# STorM32_BGC_mpu_module_v009.net
KiCad netlist of a schematic drawn in EAGLE
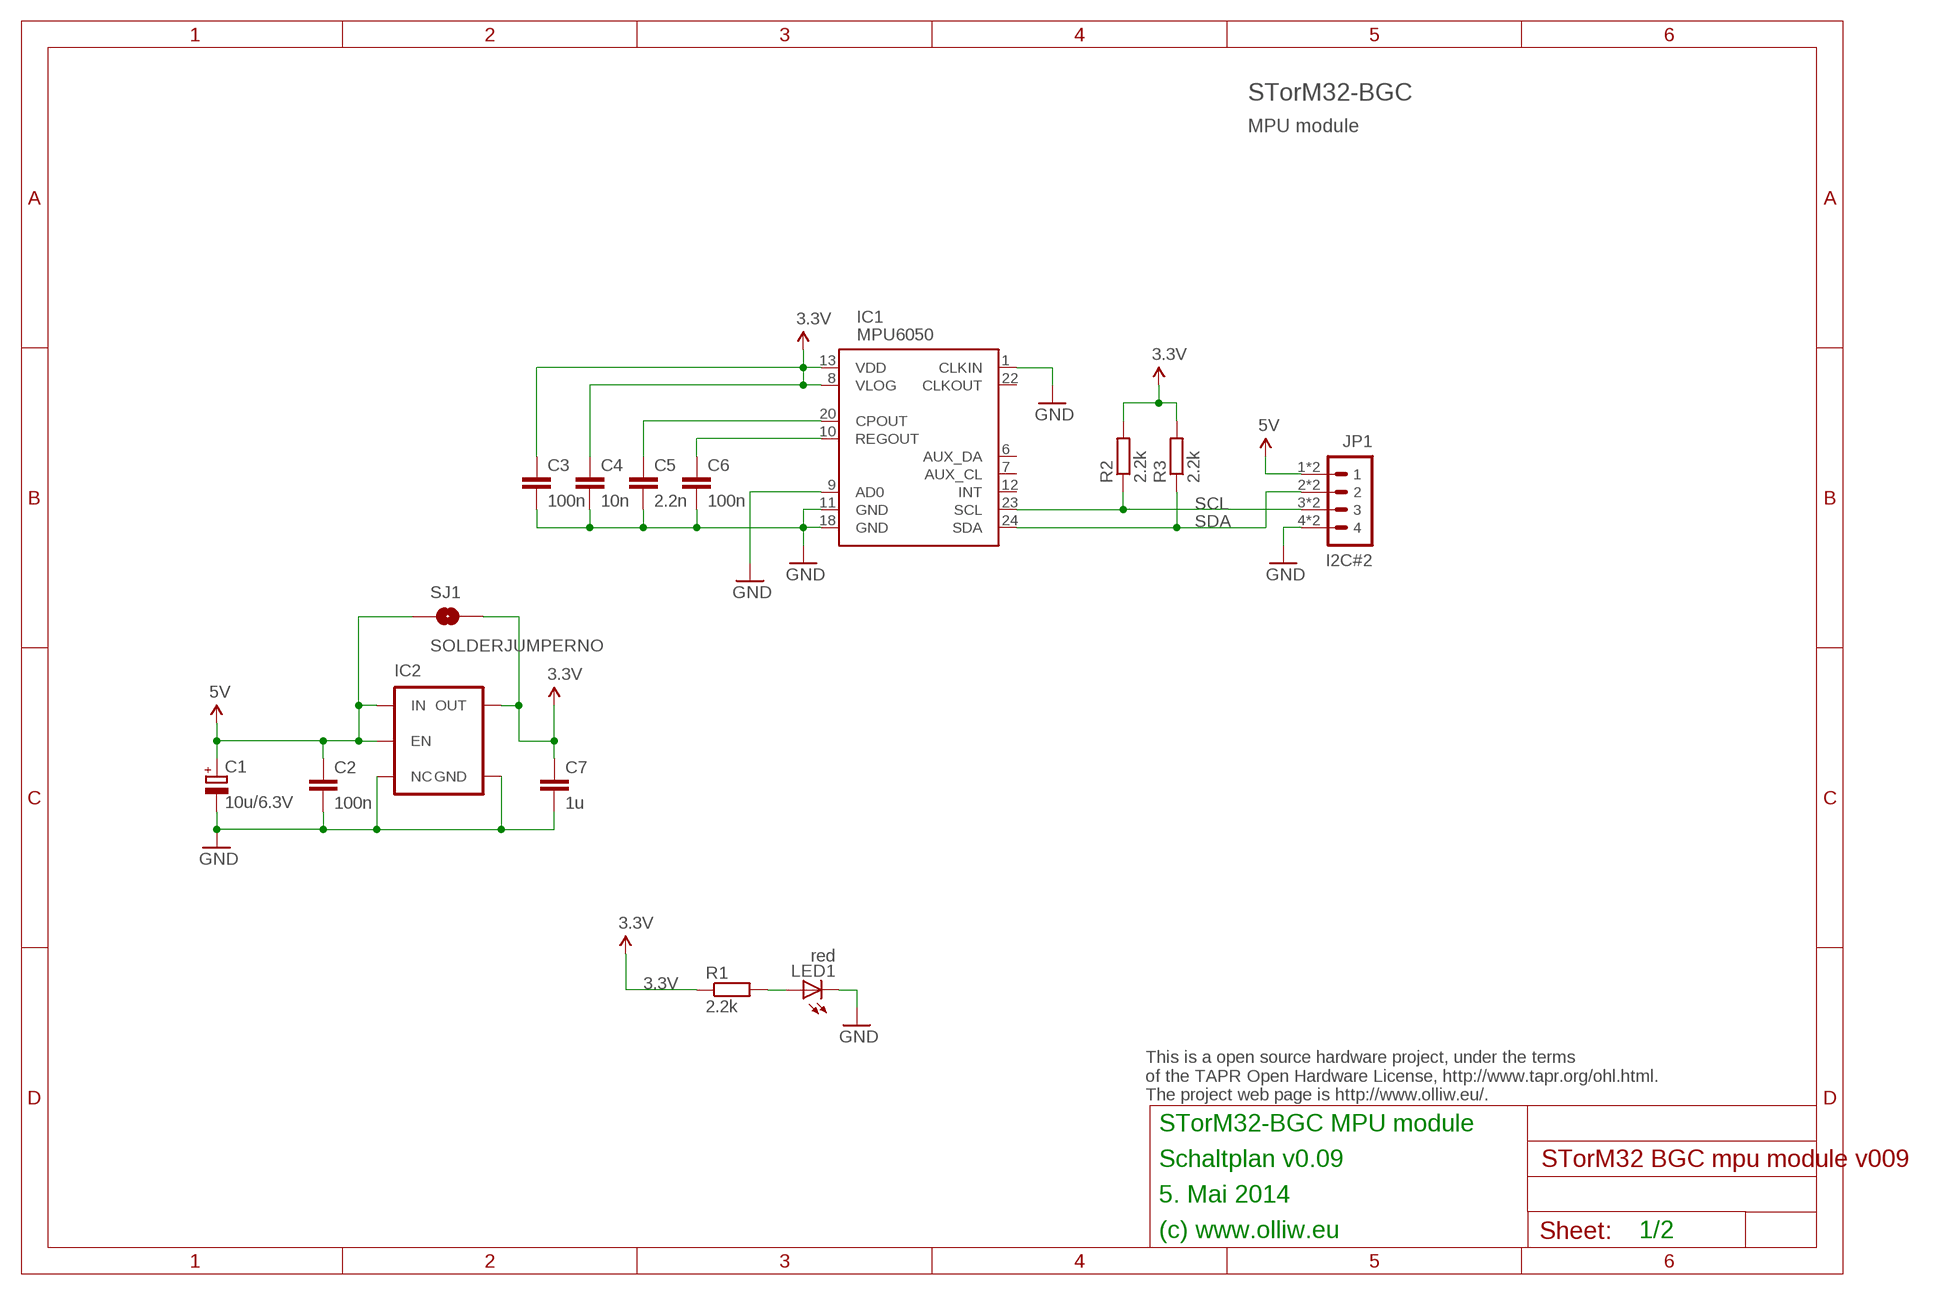
[diagram p0: schematic, sheet 1]

(export (version "E")
  (design (tool "Eeschema 10.0.6"))
  (components
    (comp (ref "C1")
      (value "10u/6.3V")
      (footprint "eagle-import:SMC_B")
      (libsource (lib "eagle-import") (part "CPOL-EUSMCB"))
    )
    (comp (ref "C2")
      (value "100n")
      (footprint "eagle-import:C0603")
      (libsource (lib "eagle-import") (part "C-EUC0603"))
    )
    (comp (ref "C3")
      (value "100n")
      (footprint "eagle-import:C0603")
      (libsource (lib "eagle-import") (part "C-EUC0603"))
    )
    (comp (ref "C4")
      (value "10n")
      (footprint "eagle-import:C0603")
      (libsource (lib "eagle-import") (part "C-EUC0603"))
    )
    (comp (ref "C5")
      (value "2.2n")
      (footprint "eagle-import:C0603")
      (libsource (lib "eagle-import") (part "C-EUC0603"))
    )
    (comp (ref "C6")
      (value "100n")
      (footprint "eagle-import:C0603")
      (libsource (lib "eagle-import") (part "C-EUC0603"))
    )
    (comp (ref "C7")
      (value "1u")
      (footprint "eagle-import:C0603")
      (libsource (lib "eagle-import") (part "C-EUC0603"))
    )
    (comp (ref "IC1")
      (value "MPU6050")
      (footprint "eagle-import:QFN-24")
      (libsource (lib "eagle-import") (part "IMU3000"))
    )
    (comp (ref "IC2")
      (value "V_REG_TPS76433SOT23-5")
      (footprint "eagle-import:SOT23-5")
      (libsource (lib "eagle-import") (part "V_REG_TPS76433SOT23-5"))
    )
    (comp (ref "JP1")
      (value "I2C#2")
      (footprint "eagle-import:MOLEX-53261-04-SMD-BOTH")
      (libsource (lib "eagle-import") (part "P4X1_1P27MOLEX-BOTH"))
    )
    (comp (ref "LED1")
      (value "red")
      (footprint "eagle-import:CHIPLED_0603")
      (libsource (lib "eagle-import") (part "LEDCHIPLED_0603"))
    )
    (comp (ref "R1")
      (value "2.2k")
      (footprint "eagle-import:R0603")
      (libsource (lib "eagle-import") (part "R-EU_R0603"))
    )
    (comp (ref "R2")
      (value "2.2k")
      (footprint "eagle-import:R0603")
      (libsource (lib "eagle-import") (part "R-EU_R0603"))
    )
    (comp (ref "R3")
      (value "2.2k")
      (footprint "eagle-import:R0603")
      (libsource (lib "eagle-import") (part "R-EU_R0603"))
    )
    (comp (ref "SJ1")
      (value "SOLDERJUMPERNO")
      (footprint "eagle-import:SJ_2S-NO")
      (libsource (lib "eagle-import") (part "SOLDERJUMPERNO"))
    )
  )
  (nets
    (net (code "1") (name "/SCL") (class "Default")
      (node (ref "IC1") (pin "23") (pinfunction "SCL_23") (pintype "bidirectional"))
      (node (ref "JP1") (pin "3") (pinfunction "3_3") (pintype "passive"))
      (node (ref "JP1") (pin "7") (pinfunction "3_7") (pintype "passive"))
      (node (ref "R2") (pin "1") (pinfunction "1_1") (pintype "passive"))
    )
    (net (code "2") (name "/SDA") (class "Default")
      (node (ref "IC1") (pin "24") (pinfunction "SDA_24") (pintype "bidirectional"))
      (node (ref "JP1") (pin "2") (pinfunction "2_2") (pintype "passive"))
      (node (ref "JP1") (pin "6") (pinfunction "2_6") (pintype "passive"))
      (node (ref "R3") (pin "1") (pinfunction "1_1") (pintype "passive"))
    )
    (net (code "3") (name "3.3V") (class "Default")
      (node (ref "C3") (pin "1") (pinfunction "1_1") (pintype "passive"))
      (node (ref "C4") (pin "1") (pinfunction "1_1") (pintype "passive"))
      (node (ref "C7") (pin "1") (pinfunction "1_1") (pintype "passive"))
      (node (ref "IC1") (pin "13") (pinfunction "VDD_13") (pintype "bidirectional"))
      (node (ref "IC1") (pin "8") (pinfunction "VLOG_8") (pintype "bidirectional"))
      (node (ref "IC2") (pin "5") (pinfunction "OUT_5") (pintype "passive"))
      (node (ref "R1") (pin "1") (pinfunction "1_1") (pintype "passive"))
      (node (ref "R2") (pin "2") (pinfunction "2_2") (pintype "passive"))
      (node (ref "R3") (pin "2") (pinfunction "2_2") (pintype "passive"))
      (node (ref "SJ1") (pin "2") (pinfunction "2_2") (pintype "passive"))
    )
    (net (code "4") (name "5V") (class "Default")
      (node (ref "C1") (pin "+") (pinfunction "+_+") (pintype "passive"))
      (node (ref "C2") (pin "1") (pinfunction "1_1") (pintype "passive"))
      (node (ref "IC2") (pin "1") (pinfunction "IN_1") (pintype "input"))
      (node (ref "IC2") (pin "3") (pinfunction "EN_3") (pintype "input"))
      (node (ref "JP1") (pin "1") (pinfunction "1_1") (pintype "passive"))
      (node (ref "JP1") (pin "5") (pinfunction "1_5") (pintype "passive"))
      (node (ref "SJ1") (pin "1") (pinfunction "1_1") (pintype "passive"))
    )
    (net (code "5") (name "GND") (class "Default")
      (node (ref "C1") (pin "-") (pinfunction "-_-") (pintype "passive"))
      (node (ref "C2") (pin "2") (pinfunction "2_2") (pintype "passive"))
      (node (ref "C3") (pin "2") (pinfunction "2_2") (pintype "passive"))
      (node (ref "C4") (pin "2") (pinfunction "2_2") (pintype "passive"))
      (node (ref "C5") (pin "2") (pinfunction "2_2") (pintype "passive"))
      (node (ref "C6") (pin "2") (pinfunction "2_2") (pintype "passive"))
      (node (ref "C7") (pin "2") (pinfunction "2_2") (pintype "passive"))
      (node (ref "IC1") (pin "1") (pinfunction "CLKIN_1") (pintype "bidirectional"))
      (node (ref "IC1") (pin "11") (pinfunction "GND_11") (pintype "bidirectional"))
      (node (ref "IC1") (pin "18") (pinfunction "GND_18") (pintype "bidirectional"))
      (node (ref "IC1") (pin "9") (pinfunction "AD0_9") (pintype "bidirectional"))
      (node (ref "IC2") (pin "2") (pinfunction "GND_2") (pintype "input"))
      (node (ref "IC2") (pin "4") (pinfunction "NC_4") (pintype "input"))
      (node (ref "JP1") (pin "4") (pinfunction "4_4") (pintype "passive"))
      (node (ref "JP1") (pin "8") (pinfunction "4_8") (pintype "passive"))
      (node (ref "LED1") (pin "C") (pinfunction "C_C") (pintype "passive"))
    )
    (net (code "6") (name "Net-(IC1-CPOUT)") (class "Default")
      (node (ref "C5") (pin "1") (pinfunction "1_1") (pintype "passive"))
      (node (ref "IC1") (pin "20") (pinfunction "CPOUT_20") (pintype "bidirectional"))
    )
    (net (code "7") (name "Net-(IC1-REGOUT)") (class "Default")
      (node (ref "C6") (pin "1") (pinfunction "1_1") (pintype "passive"))
      (node (ref "IC1") (pin "10") (pinfunction "REGOUT_10") (pintype "bidirectional"))
    )
    (net (code "8") (name "Net-(LED1-PadA)") (class "Default")
      (node (ref "LED1") (pin "A") (pinfunction "A_A") (pintype "passive"))
      (node (ref "R1") (pin "2") (pinfunction "2_2") (pintype "passive"))
    )
    (net (code "9") (name "unconnected-(IC1-AUX_CL-Pad7)") (class "Default")
      (node (ref "IC1") (pin "7") (pinfunction "AUX_CL_7") (pintype "bidirectional"))
    )
    (net (code "10") (name "unconnected-(IC1-AUX_DA-Pad6)") (class "Default")
      (node (ref "IC1") (pin "6") (pinfunction "AUX_DA_6") (pintype "bidirectional"))
    )
    (net (code "11") (name "unconnected-(IC1-CLKOUT-Pad22)") (class "Default")
      (node (ref "IC1") (pin "22") (pinfunction "CLKOUT_22") (pintype "bidirectional"))
    )
    (net (code "12") (name "unconnected-(IC1-INT-Pad12)") (class "Default")
      (node (ref "IC1") (pin "12") (pinfunction "INT_12") (pintype "bidirectional"))
    )
  )
)
